# eth_bridge_v2.net
KiCad netlist of a schematic drawn in Altium Designer
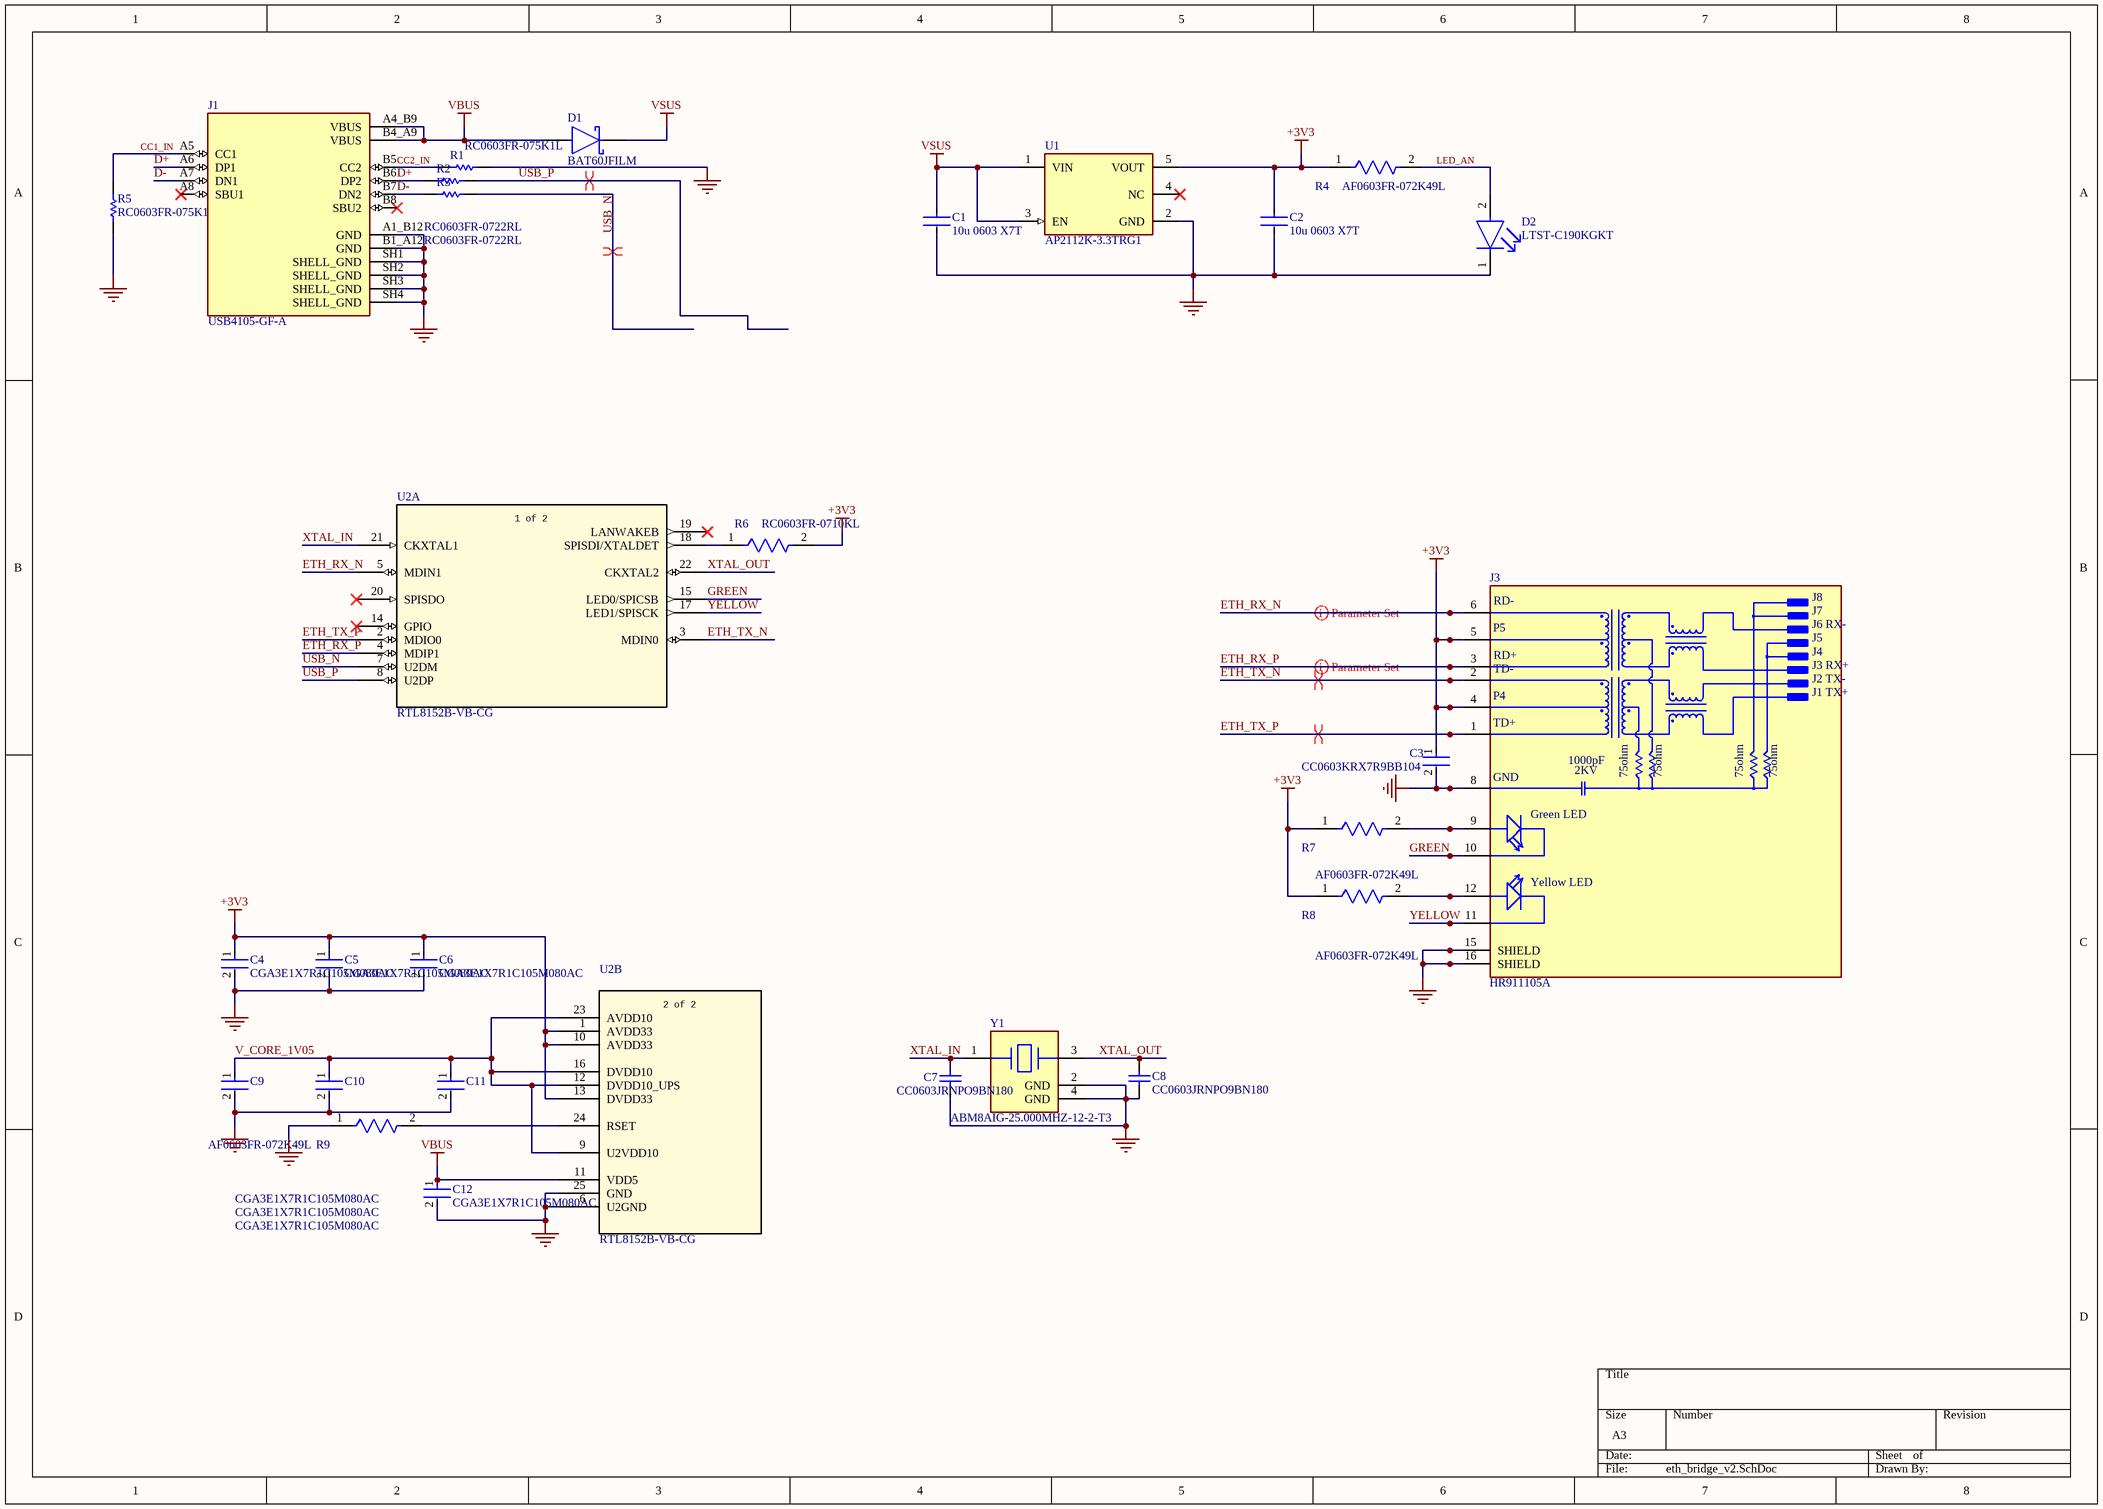
[diagram p0: eth_bridge_v2.SchDoc]

(export (version "E")
  (design (tool "Eeschema 10.0.6"))
  (components
    (comp (ref "C1")
      (value "10u 0603 X7T")
      (footprint "FP-GRM188-0_2-IPC_C")
      (description "10uF 10V X7T 0603 20%")
      (fields (field (name "TOLERANCE") "20%"))
      (libsource (lib "TIMERS_COMPONENTS") (part "CMP-06035-057161-1"))
    )
    (comp (ref "C2")
      (value "10u 0603 X7T")
      (footprint "FP-GRM188-0_2-IPC_C")
      (description "10uF 10V X7T 0603 20%")
      (fields (field (name "TOLERANCE") "20%"))
      (libsource (lib "TIMERS_COMPONENTS") (part "CMP-06035-057161-1"))
    )
    (comp (ref "C3")
      (value "CC0603KRX7R9BB104")
      (footprint "FP-CC0603-DA-MFG")
      (description "CAP CER 0.1UF 50V X7R 0603")
      (fields (field (name "MANUFACTURER") "YAGEO") (field (name "VOLTAGE") "50 V"))
      (libsource (lib "Altium Content Vault") (part "11868f565c42a9108669ba33697ecf6"))
    )
    (comp (ref "C4")
      (value "CGA3E1X7R1C105M080AC")
      (footprint "FP-CGA3E-0_3-0_1-IPC_B")
      (description "Cap Ceramic 1uF 16V X7R 20% Pad SMD 0603 +125°C Automotive T/R")
      (fields (field (name "TOLERANCE") "20%"))
      (libsource (lib "Altium Content Vault") (part "b4654b650e69147ec39a6b967a45e02"))
    )
    (comp (ref "C5")
      (value "CGA3E1X7R1C105M080AC")
      (footprint "FP-CGA3E-0_3-0_1-IPC_B")
      (description "Cap Ceramic 1uF 16V X7R 20% Pad SMD 0603 +125°C Automotive T/R")
      (fields (field (name "TOLERANCE") "20%"))
      (libsource (lib "Altium Content Vault") (part "b4654b650e69147ec39a6b967a45e02"))
    )
    (comp (ref "C6")
      (value "CGA3E1X7R1C105M080AC")
      (footprint "FP-CGA3E-0_3-0_1-IPC_B")
      (description "Cap Ceramic 1uF 16V X7R 20% Pad SMD 0603 +125°C Automotive T/R")
      (fields (field (name "TOLERANCE") "20%"))
      (libsource (lib "Altium Content Vault") (part "b4654b650e69147ec39a6b967a45e02"))
    )
    (comp (ref "C7")
      (value "CC0603JRNPO9BN180")
      (footprint "CAPC1608X90X40LL10T20")
      (description "Chip Capacitor, 18 pF, +/- 5%, 50 V, -55 to 125 degC, 0603 (1608 Metric), RoHS, Tape and Reel")
      (fields (field (name "TOLERANCE") "1%"))
      (libsource (lib "Altium Content Vault") (part "CAP-NP-2"))
    )
    (comp (ref "C8")
      (value "CC0603JRNPO9BN180")
      (footprint "CAPC1608X90X40LL10T20")
      (description "Chip Capacitor, 18 pF, +/- 5%, 50 V, -55 to 125 degC, 0603 (1608 Metric), RoHS, Tape and Reel")
      (fields (field (name "TOLERANCE") "1%"))
      (libsource (lib "Altium Content Vault") (part "CAP-NP-2"))
    )
    (comp (ref "C9")
      (value "CGA3E1X7R1C105M080AC")
      (footprint "FP-CGA3E-0_3-0_1-IPC_B")
      (description "Cap Ceramic 1uF 16V X7R 20% Pad SMD 0603 +125°C Automotive T/R")
      (fields (field (name "TOLERANCE") "20%"))
      (libsource (lib "Altium Content Vault") (part "b4654b650e69147ec39a6b967a45e02"))
    )
    (comp (ref "C10")
      (value "CGA3E1X7R1C105M080AC")
      (footprint "FP-CGA3E-0_3-0_1-IPC_B")
      (description "Cap Ceramic 1uF 16V X7R 20% Pad SMD 0603 +125°C Automotive T/R")
      (fields (field (name "TOLERANCE") "20%"))
      (libsource (lib "Altium Content Vault") (part "b4654b650e69147ec39a6b967a45e02"))
    )
    (comp (ref "C11")
      (value "CGA3E1X7R1C105M080AC")
      (footprint "FP-CGA3E-0_3-0_1-IPC_B")
      (description "Cap Ceramic 1uF 16V X7R 20% Pad SMD 0603 +125°C Automotive T/R")
      (fields (field (name "TOLERANCE") "20%"))
      (libsource (lib "Altium Content Vault") (part "b4654b650e69147ec39a6b967a45e02"))
    )
    (comp (ref "C12")
      (value "CGA3E1X7R1C105M080AC")
      (footprint "FP-CGA3E-0_3-0_1-IPC_B")
      (description "Cap Ceramic 1uF 16V X7R 20% Pad SMD 0603 +125°C Automotive T/R")
      (fields (field (name "TOLERANCE") "20%"))
      (libsource (lib "Altium Content Vault") (part "b4654b650e69147ec39a6b967a45e02"))
    )
    (comp (ref "D1")
      (value "BAT60JFILM")
      (footprint "FP-BAT60JFILM-MFG")
      (description "SCHOTTKY 10V 3A SOD323")
      (libsource (lib "TIMERS_COMPONENTS") (part "CMP-12187-000028-1"))
    )
    (comp (ref "D2")
      (value "LTST-C190KGKT")
      (footprint "FP-LTST-C190KGKT-MFG")
      (description "LED GREEN CLEAR CHIP SMD")
      (libsource (lib "Altium Content Vault") (part "8706943c75ba83719d021d2fdc84c58"))
    )
    (comp (ref "J1")
      (value "USB4105-GF-A")
      (footprint "GCT_USB4105-GF-A")
      (description "USB-C")
      (fields (field (name "MF") "{'manufacturer': u'GCT'}"))
      (libsource (lib "eth_bridge_v2") (part "CMP-007-000001-1"))
    )
    (comp (ref "J3")
      (value "HR911105A")
      (footprint "HANRUN_HR911105A")
      (description "DIP RJ45 Connector;")
      (fields (field (name "MF") "hanrun"))
      (libsource (lib "eth_bridge_v2") (part "CMP-002-00071-1"))
    )
    (comp (ref "R1")
      (value "RC0603FR-075K1L")
      (footprint "RESC1608X55X25ML10T15")
      (fields (field (name "MANUFACTURER") "Yageo"))
      (libsource (lib "Altium Content Vault") (part "RES"))
    )
    (comp (ref "R2")
      (value "RC0603FR-0722RL")
      (footprint "RESC1608X55X25NL10T15")
      (description "Chip Resistor, 22 Ohm, +/- 1%, 0.1 W, -55 to 155 degC, 0603 (1608 Metric), RoHS, Tape and Reel")
      (libsource (lib "Altium Content Vault") (part "RES-2"))
    )
    (comp (ref "R3")
      (value "RC0603FR-0722RL")
      (footprint "RESC1608X55X25NL10T15")
      (description "Chip Resistor, 22 Ohm, +/- 1%, 0.1 W, -55 to 155 degC, 0603 (1608 Metric), RoHS, Tape and Reel")
      (libsource (lib "Altium Content Vault") (part "RES-2"))
    )
    (comp (ref "R4")
      (value "AF0603FR-072K49L")
      (footprint "FP-AF0603-IPC_A")
      (description "Anti-Sulfurated Chip Resistors Automotive Grade 2.49kΩ 1% 100ppm/°C 0603")
      (fields (field (name "TOLERANCE") "1%"))
      (libsource (lib "Altium Content Vault") (part "1029c3af85768c4190bb7ad29bc67b5"))
    )
    (comp (ref "R5")
      (value "RC0603FR-075K1L")
      (footprint "RESC1608X55X25ML10T15")
      (fields (field (name "MANUFACTURER") "Yageo"))
      (libsource (lib "Altium Content Vault") (part "RES"))
    )
    (comp (ref "R6")
      (value "RC0603FR-0710KL")
      (footprint "FP-RC0603-0_55-IPC_C")
      (description "RES 10K OHM 1% 1/10W 0603")
      (fields (field (name "TOLERANCE") "1%"))
      (libsource (lib "Altium Content Vault") (part "1029c3af85768c4190bb7ad29bc67b5"))
    )
    (comp (ref "R7")
      (value "AF0603FR-072K49L")
      (footprint "FP-AF0603-IPC_A")
      (description "Anti-Sulfurated Chip Resistors Automotive Grade 2.49kΩ 1% 100ppm/°C 0603")
      (fields (field (name "TOLERANCE") "1%"))
      (libsource (lib "Altium Content Vault") (part "1029c3af85768c4190bb7ad29bc67b5"))
    )
    (comp (ref "R8")
      (value "AF0603FR-072K49L")
      (footprint "FP-AF0603-IPC_A")
      (description "Anti-Sulfurated Chip Resistors Automotive Grade 2.49kΩ 1% 100ppm/°C 0603")
      (fields (field (name "TOLERANCE") "1%"))
      (libsource (lib "Altium Content Vault") (part "1029c3af85768c4190bb7ad29bc67b5"))
    )
    (comp (ref "R9")
      (value "AF0603FR-072K49L")
      (footprint "FP-AF0603-IPC_A")
      (description "Anti-Sulfurated Chip Resistors Automotive Grade 2.49kΩ 1% 100ppm/°C 0603")
      (fields (field (name "TOLERANCE") "1%"))
      (libsource (lib "Altium Content Vault") (part "1029c3af85768c4190bb7ad29bc67b5"))
    )
    (comp (ref "U1")
      (value "AP2112K-3.3TRG1")
      (footprint "FP-SOT25-IPC_A")
      (description "LDO 3.3V 600MA SOT25")
      (libsource (lib "eth_bridge_v2") (part "CMP-12756-000035-1"))
    )
    (comp (ref "U2")
      (value "RTL8152B-VB-CG")
      (footprint "RTL8152B-VB-CG_RTK")
      (description "Description")
      (fields (field (name "COPYRIGHT") "Copyright (C) 2026 Ultra Librarian. All rights reserved."))
      (libsource (lib "RTL8152B-VB-CG") (part "RTL8152B-VB-CG"))
    )
    (comp (ref "Y1")
      (value "ABM8AIG-25.000MHZ-12-2-T3")
      (footprint "FP-ABM8AIG-MFG")
      (description "Crystal 25MHz ±20ppm (Tol) ±100ppm (Stability) 12pF FUND 50Ω Automotive 4-Pin Ultra Mini-CSMD T/R")
      (libsource (lib "Altium Content Vault") (part "5645ab55de99a04feaa93ac4102b7fe"))
    )
  )
  (nets
    (net (code "1") (name "+3V3") (class "Default")
      (node (ref "C2") (pin "1") (pinfunction "1_1") (pintype "passive"))
      (node (ref "C3") (pin "1") (pinfunction "1_1") (pintype "passive"))
      (node (ref "C4") (pin "1") (pinfunction "1_1") (pintype "passive"))
      (node (ref "C5") (pin "1") (pinfunction "1_1") (pintype "passive"))
      (node (ref "C6") (pin "1") (pinfunction "1_1") (pintype "passive"))
      (node (ref "J3") (pin "4") (pinfunction "P4_4") (pintype "passive"))
      (node (ref "J3") (pin "5") (pinfunction "P5_5") (pintype "passive"))
      (node (ref "R4") (pin "1") (pinfunction "1_1") (pintype "passive"))
      (node (ref "R6") (pin "2") (pinfunction "2_2") (pintype "passive"))
      (node (ref "R7") (pin "1") (pinfunction "1_1") (pintype "passive"))
      (node (ref "R8") (pin "1") (pinfunction "1_1") (pintype "passive"))
      (node (ref "U1") (pin "5") (pinfunction "VOUT_5") (pintype "power_in"))
      (node (ref "U2") (pin "1") (pinfunction "AVDD33_1") (pintype "power_in"))
      (node (ref "U2") (pin "10") (pinfunction "AVDD33_10") (pintype "power_in"))
      (node (ref "U2") (pin "13") (pinfunction "DVDD33_13") (pintype "power_in"))
    )
    (net (code "2") (name "/CC1_IN") (class "Default")
      (node (ref "J1") (pin "A5") (pinfunction "CC1_A5") (pintype "bidirectional"))
      (node (ref "R5") (pin "2") (pinfunction "2_2") (pintype "passive"))
    )
    (net (code "3") (name "/CC2_IN") (class "Default")
      (node (ref "J1") (pin "B5") (pinfunction "CC2_B5") (pintype "bidirectional"))
      (node (ref "R1") (pin "1") (pinfunction "1_1") (pintype "passive"))
    )
    (net (code "4") (name "/D+") (class "Default")
      (node (ref "J1") (pin "A6") (pinfunction "DP1_A6") (pintype "bidirectional"))
      (node (ref "J1") (pin "B6") (pinfunction "DP2_B6") (pintype "bidirectional"))
      (node (ref "R2") (pin "1") (pinfunction "1_1") (pintype "passive"))
    )
    (net (code "5") (name "/D-") (class "Default")
      (node (ref "J1") (pin "A7") (pinfunction "DN1_A7") (pintype "bidirectional"))
      (node (ref "J1") (pin "B7") (pinfunction "DN2_B7") (pintype "bidirectional"))
      (node (ref "R3") (pin "1") (pinfunction "1_1") (pintype "passive"))
    )
    (net (code "6") (name "/ETH_RX_N") (class "Default")
      (node (ref "J3") (pin "6") (pinfunction "RD-_6") (pintype "passive"))
      (node (ref "U2") (pin "5") (pinfunction "MDIN1_5") (pintype "bidirectional"))
    )
    (net (code "7") (name "/ETH_RX_P") (class "Default")
      (node (ref "J3") (pin "3") (pinfunction "RD+_3") (pintype "passive"))
      (node (ref "U2") (pin "4") (pinfunction "MDIP1_4") (pintype "bidirectional"))
    )
    (net (code "8") (name "/ETH_TX_N") (class "Default")
      (node (ref "J3") (pin "2") (pinfunction "TD-_2") (pintype "passive"))
      (node (ref "U2") (pin "3") (pinfunction "MDIN0_3") (pintype "bidirectional"))
    )
    (net (code "9") (name "/ETH_TX_P") (class "Default")
      (node (ref "J3") (pin "1") (pinfunction "TD+_1") (pintype "passive"))
      (node (ref "U2") (pin "2") (pinfunction "MDIO0_2") (pintype "bidirectional"))
    )
    (net (code "10") (name "/GREEN") (class "Default")
      (node (ref "J3") (pin "10") (pinfunction "GC_10") (pintype "passive"))
      (node (ref "U2") (pin "15") (pinfunction "LED0/SPICSB_15") (pintype "output"))
    )
    (net (code "11") (name "/LED_AN") (class "Default")
      (node (ref "D2") (pin "2") (pinfunction "A_2") (pintype "passive"))
      (node (ref "R4") (pin "2") (pinfunction "2_2") (pintype "passive"))
    )
    (net (code "12") (name "/USB_N") (class "Default")
      (node (ref "R3") (pin "2") (pinfunction "2_2") (pintype "passive"))
      (node (ref "U2") (pin "7") (pinfunction "U2DM_7") (pintype "bidirectional"))
    )
    (net (code "13") (name "/USB_P") (class "Default")
      (node (ref "R2") (pin "2") (pinfunction "2_2") (pintype "passive"))
      (node (ref "U2") (pin "8") (pinfunction "U2DP_8") (pintype "bidirectional"))
    )
    (net (code "14") (name "/V_CORE_1V05") (class "Default")
      (node (ref "C10") (pin "1") (pinfunction "1_1") (pintype "passive"))
      (node (ref "C11") (pin "1") (pinfunction "1_1") (pintype "passive"))
      (node (ref "C9") (pin "1") (pinfunction "1_1") (pintype "passive"))
      (node (ref "U2") (pin "12") (pinfunction "DVDD10_UPS_12") (pintype "power_in"))
      (node (ref "U2") (pin "16") (pinfunction "DVDD10_16") (pintype "power_in"))
      (node (ref "U2") (pin "23") (pinfunction "AVDD10_23") (pintype "power_in"))
      (node (ref "U2") (pin "9") (pinfunction "U2VDD10_9") (pintype "power_in"))
    )
    (net (code "15") (name "/XTAL_IN") (class "Default")
      (node (ref "C7") (pin "2") (pinfunction "2_2") (pintype "passive"))
      (node (ref "U2") (pin "21") (pinfunction "CKXTAL1_21") (pintype "input"))
      (node (ref "Y1") (pin "1") (pinfunction "1_1") (pintype "passive"))
    )
    (net (code "16") (name "/XTAL_OUT") (class "Default")
      (node (ref "C8") (pin "2") (pinfunction "2_2") (pintype "passive"))
      (node (ref "U2") (pin "22") (pinfunction "CKXTAL2_22") (pintype "bidirectional"))
      (node (ref "Y1") (pin "3") (pinfunction "3_3") (pintype "passive"))
    )
    (net (code "17") (name "/YELLOW") (class "Default")
      (node (ref "J3") (pin "11") (pinfunction "YC_11") (pintype "passive"))
      (node (ref "U2") (pin "17") (pinfunction "LED1/SPISCK_17") (pintype "output"))
    )
    (net (code "18") (name "GND") (class "Default")
      (node (ref "C1") (pin "2") (pinfunction "2_2") (pintype "passive"))
      (node (ref "C10") (pin "2") (pinfunction "2_2") (pintype "passive"))
      (node (ref "C11") (pin "2") (pinfunction "2_2") (pintype "passive"))
      (node (ref "C12") (pin "2") (pinfunction "2_2") (pintype "passive"))
      (node (ref "C2") (pin "2") (pinfunction "2_2") (pintype "passive"))
      (node (ref "C3") (pin "2") (pinfunction "2_2") (pintype "passive"))
      (node (ref "C4") (pin "2") (pinfunction "2_2") (pintype "passive"))
      (node (ref "C5") (pin "2") (pinfunction "2_2") (pintype "passive"))
      (node (ref "C6") (pin "2") (pinfunction "2_2") (pintype "passive"))
      (node (ref "C7") (pin "1") (pinfunction "1_1") (pintype "passive"))
      (node (ref "C8") (pin "1") (pinfunction "1_1") (pintype "passive"))
      (node (ref "C9") (pin "2") (pinfunction "2_2") (pintype "passive"))
      (node (ref "D2") (pin "1") (pinfunction "C_1") (pintype "passive"))
      (node (ref "J1") (pin "A1_B12") (pinfunction "GND_A1_B12") (pintype "power_in"))
      (node (ref "J1") (pin "B1_A12") (pinfunction "GND_B1_A12") (pintype "power_in"))
      (node (ref "J1") (pin "SH1") (pinfunction "SHELL_GND_SH1") (pintype "power_in"))
      (node (ref "J1") (pin "SH2") (pinfunction "SHELL_GND_SH2") (pintype "power_in"))
      (node (ref "J1") (pin "SH3") (pinfunction "SHELL_GND_SH3") (pintype "power_in"))
      (node (ref "J1") (pin "SH4") (pinfunction "SHELL_GND_SH4") (pintype "power_in"))
      (node (ref "J3") (pin "15") (pinfunction "SHIELD_15") (pintype "passive"))
      (node (ref "J3") (pin "16") (pinfunction "SHIELD_16") (pintype "passive"))
      (node (ref "J3") (pin "8") (pinfunction "GND_8") (pintype "power_in"))
      (node (ref "R1") (pin "2") (pinfunction "2_2") (pintype "passive"))
      (node (ref "R5") (pin "1") (pinfunction "1_1") (pintype "passive"))
      (node (ref "R9") (pin "1") (pinfunction "1_1") (pintype "passive"))
      (node (ref "U1") (pin "2") (pinfunction "GND_2") (pintype "power_in"))
      (node (ref "U2") (pin "25") (pinfunction "GND_25") (pintype "power_in"))
      (node (ref "U2") (pin "6") (pinfunction "U2GND_6") (pintype "power_in"))
      (node (ref "Y1") (pin "2") (pinfunction "GND_2") (pintype "power_in"))
      (node (ref "Y1") (pin "4") (pinfunction "GND_4") (pintype "power_in"))
    )
    (net (code "19") (name "Net-(J3-GA)") (class "Default")
      (node (ref "J3") (pin "9") (pinfunction "GA_9") (pintype "passive"))
      (node (ref "R7") (pin "2") (pinfunction "2_2") (pintype "passive"))
    )
    (net (code "20") (name "Net-(J3-YA)") (class "Default")
      (node (ref "J3") (pin "12") (pinfunction "YA_12") (pintype "passive"))
      (node (ref "R8") (pin "2") (pinfunction "2_2") (pintype "passive"))
    )
    (net (code "21") (name "Net-(U2A-SPISDI{slash}XTALDET)") (class "Default")
      (node (ref "R6") (pin "1") (pinfunction "1_1") (pintype "passive"))
      (node (ref "U2") (pin "18") (pinfunction "SPISDI/XTALDET_18") (pintype "output"))
    )
    (net (code "22") (name "Net-(U2B-RSET)") (class "Default")
      (node (ref "R9") (pin "2") (pinfunction "2_2") (pintype "passive"))
      (node (ref "U2") (pin "24") (pinfunction "RSET_24") (pintype "power_in"))
    )
    (net (code "23") (name "VBUS") (class "Default")
      (node (ref "C12") (pin "1") (pinfunction "1_1") (pintype "passive"))
      (node (ref "D1") (pin "2") (pinfunction "A_2") (pintype "passive"))
      (node (ref "J1") (pin "A4_B9") (pinfunction "VBUS_A4_B9") (pintype "power_in"))
      (node (ref "J1") (pin "B4_A9") (pinfunction "VBUS_B4_A9") (pintype "power_in"))
      (node (ref "U2") (pin "11") (pinfunction "VDD5_11") (pintype "power_in"))
    )
    (net (code "24") (name "VSUS") (class "Default")
      (node (ref "C1") (pin "1") (pinfunction "1_1") (pintype "passive"))
      (node (ref "D1") (pin "1") (pinfunction "K_1") (pintype "passive"))
      (node (ref "U1") (pin "1") (pinfunction "VIN_1") (pintype "power_in"))
      (node (ref "U1") (pin "3") (pinfunction "EN_3") (pintype "input"))
    )
    (net (code "25") (name "unconnected-(J1-SBU1-PadA8)") (class "Default")
      (node (ref "J1") (pin "A8") (pinfunction "SBU1_A8") (pintype "bidirectional+no_connect"))
    )
    (net (code "26") (name "unconnected-(J1-SBU2-PadB8)") (class "Default")
      (node (ref "J1") (pin "B8") (pinfunction "SBU2_B8") (pintype "bidirectional+no_connect"))
    )
    (net (code "27") (name "unconnected-(U1-NC-Pad4)") (class "Default")
      (node (ref "U1") (pin "4") (pinfunction "NC_4") (pintype "passive+no_connect"))
    )
    (net (code "28") (name "unconnected-(U2A-GPIO-Pad14)") (class "Default")
      (node (ref "U2") (pin "14") (pinfunction "GPIO_14") (pintype "bidirectional+no_connect"))
    )
    (net (code "29") (name "unconnected-(U2A-LANWAKEB-Pad19)") (class "Default")
      (node (ref "U2") (pin "19") (pinfunction "LANWAKEB_19") (pintype "output+no_connect"))
    )
    (net (code "30") (name "unconnected-(U2A-SPISDO-Pad20)") (class "Default")
      (node (ref "U2") (pin "20") (pinfunction "SPISDO_20") (pintype "input+no_connect"))
    )
  )
)
